# ver_2.net
KiCad netlist of a schematic drawn in EAGLE
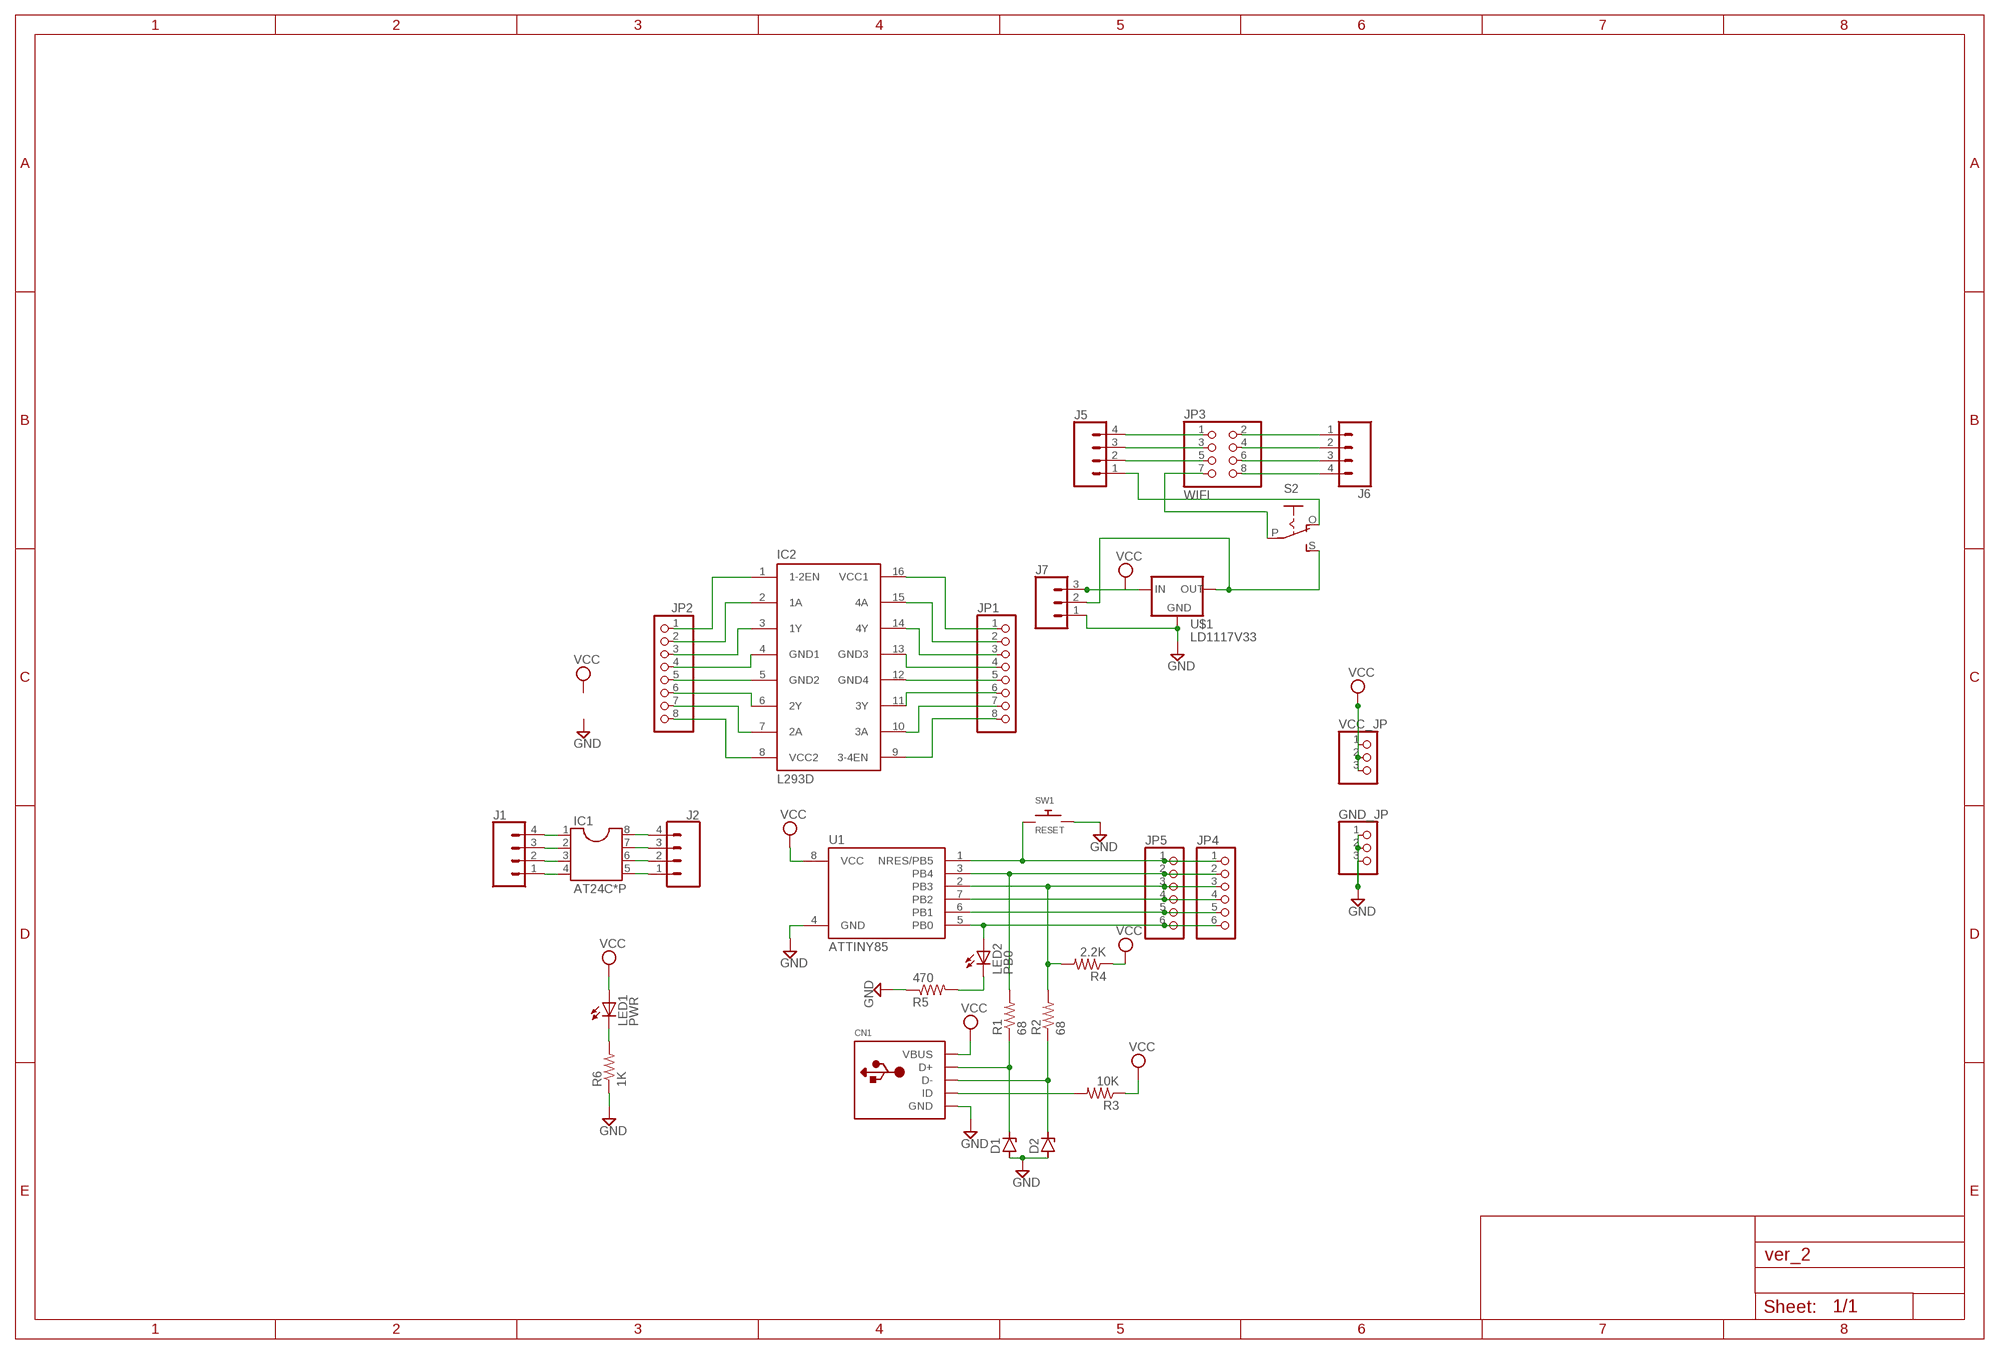
[diagram p0: schematic, sheet 1]

(export (version "E")
  (design (tool "Eeschema 10.0.6"))
  (components
    (comp (ref "CN1")
      (value "USBTHM")
      (footprint "eagle-import:USB-MINIB-THM")
      (libsource (lib "eagle-import") (part "USBTHM"))
    )
    (comp (ref "D1")
      (value "ZENER-DIODEDO34-7")
      (footprint "eagle-import:DO34Z7")
      (libsource (lib "eagle-import") (part "ZENER-DIODEDO34-7"))
    )
    (comp (ref "D2")
      (value "ZENER-DIODEDO34-7")
      (footprint "eagle-import:DO34Z7")
      (libsource (lib "eagle-import") (part "ZENER-DIODEDO34-7"))
    )
    (comp (ref "GND_JP")
      (value "PINHD-1X3")
      (footprint "eagle-import:1X03")
      (libsource (lib "eagle-import") (part "PINHD-1X3"))
    )
    (comp (ref "IC1")
      (value "AT24C*P")
      (footprint "eagle-import:SOCKET-08")
      (libsource (lib "eagle-import") (part "DIL8S"))
    )
    (comp (ref "IC2")
      (value "L293D")
      (footprint "eagle-import:DIL16")
      (libsource (lib "eagle-import") (part "L293D"))
    )
    (comp (ref "J1")
      (value "CONN_041X04_NO_SILK")
      (footprint "eagle-import:1X04_NO_SILK")
      (libsource (lib "eagle-import") (part "CONN_041X04_NO_SILK"))
    )
    (comp (ref "J2")
      (value "CONN_041X04_NO_SILK")
      (footprint "eagle-import:1X04_NO_SILK")
      (libsource (lib "eagle-import") (part "CONN_041X04_NO_SILK"))
    )
    (comp (ref "J5")
      (value "CONN_04PTH")
      (footprint "eagle-import:1X04")
      (libsource (lib "eagle-import") (part "CONN_04PTH"))
    )
    (comp (ref "J6")
      (value "CONN_04PTH")
      (footprint "eagle-import:1X04")
      (libsource (lib "eagle-import") (part "CONN_04PTH"))
    )
    (comp (ref "J7")
      (value "CONN_03")
      (footprint "eagle-import:1X03")
      (libsource (lib "eagle-import") (part "CONN_03"))
    )
    (comp (ref "JP1")
      (value "PINHD-1X8CLEANBIG")
      (footprint "eagle-import:1X08-CLEANBIG")
      (libsource (lib "eagle-import") (part "PINHD-1X8CLEANBIG"))
    )
    (comp (ref "JP2")
      (value "PINHD-1X8CLEANBIG")
      (footprint "eagle-import:1X08-CLEANBIG")
      (libsource (lib "eagle-import") (part "PINHD-1X8CLEANBIG"))
    )
    (comp (ref "JP3")
      (value "WIFI")
      (footprint "eagle-import:2X04")
      (libsource (lib "eagle-import") (part "PINHD-2X4"))
    )
    (comp (ref "JP4")
      (value "PINHD-1X6")
      (footprint "eagle-import:1X06")
      (libsource (lib "eagle-import") (part "PINHD-1X6"))
    )
    (comp (ref "JP5")
      (value "PINHD-1X6")
      (footprint "eagle-import:1X06")
      (libsource (lib "eagle-import") (part "PINHD-1X6"))
    )
    (comp (ref "LED1")
      (value "PWR")
      (footprint "eagle-import:LED3MM")
      (libsource (lib "eagle-import") (part "LED3MM"))
    )
    (comp (ref "LED2")
      (value "PB0")
      (footprint "eagle-import:LED3MM")
      (libsource (lib "eagle-import") (part "LED3MM"))
    )
    (comp (ref "R1")
      (value "68")
      (footprint "eagle-import:0204V")
      (libsource (lib "eagle-import") (part "R-US_0204/2V"))
    )
    (comp (ref "R2")
      (value "68")
      (footprint "eagle-import:0204V")
      (libsource (lib "eagle-import") (part "R-US_0204/2V"))
    )
    (comp (ref "R3")
      (value "10K")
      (footprint "eagle-import:0204V")
      (libsource (lib "eagle-import") (part "R-US_0204/2V"))
    )
    (comp (ref "R4")
      (value "2.2K")
      (footprint "eagle-import:0204V")
      (libsource (lib "eagle-import") (part "R-US_0204/2V"))
    )
    (comp (ref "R5")
      (value "470")
      (footprint "eagle-import:0204V")
      (libsource (lib "eagle-import") (part "R-US_0204/2V"))
    )
    (comp (ref "R6")
      (value "1K")
      (footprint "eagle-import:0204V")
      (libsource (lib "eagle-import") (part "R-US_0204/2V"))
    )
    (comp (ref "S2")
      (value "EG1218S")
      (footprint "eagle-import:EG1218")
      (libsource (lib "eagle-import") (part "EG1218S"))
    )
    (comp (ref "SW1")
      (value "RESET")
      (footprint "eagle-import:TACT_PANA-EVQ")
      (libsource (lib "eagle-import") (part "SWITCH_PUSHBUTTONEVQ-PE"))
    )
    (comp (ref "U$1")
      (value "LD1117V33")
      (footprint "eagle-import:LD1117V33")
      (libsource (lib "eagle-import") (part "LD1117V33"))
    )
    (comp (ref "U1")
      (value "ATTINY85")
      (footprint "eagle-import:PDIP08_300MIL")
      (libsource (lib "eagle-import") (part "ATTINY85P-20"))
    )
    (comp (ref "VCC_JP")
      (value "PINHD-1X3")
      (footprint "eagle-import:1X03")
      (libsource (lib "eagle-import") (part "PINHD-1X3"))
    )
  )
  (nets
    (net (code "1") (name "GND") (class "Default")
      (node (ref "CN1") (pin "GND") (pinfunction "GND_GND") (pintype "power_in"))
      (node (ref "D1") (pin "A") (pinfunction "A_A") (pintype "passive"))
      (node (ref "D2") (pin "A") (pinfunction "A_A") (pintype "passive"))
      (node (ref "GND_JP") (pin "1") (pinfunction "1_1") (pintype "passive"))
      (node (ref "GND_JP") (pin "2") (pinfunction "2_2") (pintype "passive"))
      (node (ref "GND_JP") (pin "3") (pinfunction "3_3") (pintype "passive"))
      (node (ref "J7") (pin "1") (pinfunction "1_1") (pintype "passive"))
      (node (ref "R5") (pin "1") (pinfunction "1_1") (pintype "passive"))
      (node (ref "R6") (pin "1") (pinfunction "1_1") (pintype "passive"))
      (node (ref "SW1") (pin "P$2") (pinfunction "P$2_P$2") (pintype "passive"))
      (node (ref "U$1") (pin "GND") (pinfunction "GND_GND") (pintype "input"))
      (node (ref "U1") (pin "4") (pinfunction "GND_4") (pintype "power_in"))
    )
    (net (code "2") (name "Net-(CN1-PadD+)") (class "Default")
      (node (ref "CN1") (pin "D+") (pinfunction "D+_D+") (pintype "bidirectional"))
      (node (ref "D1") (pin "C") (pinfunction "C_C") (pintype "passive"))
      (node (ref "R1") (pin "1") (pinfunction "1_1") (pintype "passive"))
    )
    (net (code "3") (name "Net-(CN1-PadD-)") (class "Default")
      (node (ref "CN1") (pin "D-") (pinfunction "D-_D-") (pintype "bidirectional"))
      (node (ref "D2") (pin "C") (pinfunction "C_C") (pintype "passive"))
      (node (ref "R2") (pin "1") (pinfunction "1_1") (pintype "passive"))
    )
    (net (code "4") (name "Net-(CN1-PadID)") (class "Default")
      (node (ref "CN1") (pin "ID") (pinfunction "ID_ID") (pintype "bidirectional"))
      (node (ref "R3") (pin "2") (pinfunction "2_2") (pintype "passive"))
    )
    (net (code "5") (name "Net-(IC1-Pad1)") (class "Default")
      (node (ref "IC1") (pin "1") (pinfunction "1_1") (pintype "passive"))
      (node (ref "J1") (pin "4") (pinfunction "4_4") (pintype "passive"))
    )
    (net (code "6") (name "Net-(IC1-Pad2)") (class "Default")
      (node (ref "IC1") (pin "2") (pinfunction "2_2") (pintype "passive"))
      (node (ref "J1") (pin "3") (pinfunction "3_3") (pintype "passive"))
    )
    (net (code "7") (name "Net-(IC1-Pad3)") (class "Default")
      (node (ref "IC1") (pin "3") (pinfunction "3_3") (pintype "passive"))
      (node (ref "J1") (pin "2") (pinfunction "2_2") (pintype "passive"))
    )
    (net (code "8") (name "Net-(IC1-Pad4)") (class "Default")
      (node (ref "IC1") (pin "4") (pinfunction "4_4") (pintype "passive"))
      (node (ref "J1") (pin "1") (pinfunction "1_1") (pintype "passive"))
    )
    (net (code "9") (name "Net-(IC1-Pad5)") (class "Default")
      (node (ref "IC1") (pin "5") (pinfunction "5_5") (pintype "passive"))
      (node (ref "J2") (pin "1") (pinfunction "1_1") (pintype "passive"))
    )
    (net (code "10") (name "Net-(IC1-Pad6)") (class "Default")
      (node (ref "IC1") (pin "6") (pinfunction "6_6") (pintype "passive"))
      (node (ref "J2") (pin "2") (pinfunction "2_2") (pintype "passive"))
    )
    (net (code "11") (name "Net-(IC1-Pad7)") (class "Default")
      (node (ref "IC1") (pin "7") (pinfunction "7_7") (pintype "passive"))
      (node (ref "J2") (pin "3") (pinfunction "3_3") (pintype "passive"))
    )
    (net (code "12") (name "Net-(IC1-Pad8)") (class "Default")
      (node (ref "IC1") (pin "8") (pinfunction "8_8") (pintype "passive"))
      (node (ref "J2") (pin "4") (pinfunction "4_4") (pintype "passive"))
    )
    (net (code "13") (name "Net-(IC2-1-2EN)") (class "Default")
      (node (ref "IC2") (pin "1") (pinfunction "1-2EN_1") (pintype "input"))
      (node (ref "JP2") (pin "1") (pinfunction "1_1") (pintype "passive"))
    )
    (net (code "14") (name "Net-(IC2-1A)") (class "Default")
      (node (ref "IC2") (pin "2") (pinfunction "1A_2") (pintype "input"))
      (node (ref "JP2") (pin "2") (pinfunction "2_2") (pintype "passive"))
    )
    (net (code "15") (name "Net-(IC2-1Y)") (class "Default")
      (node (ref "IC2") (pin "3") (pinfunction "1Y_3") (pintype "output"))
      (node (ref "JP2") (pin "3") (pinfunction "3_3") (pintype "passive"))
    )
    (net (code "16") (name "Net-(IC2-2A)") (class "Default")
      (node (ref "IC2") (pin "7") (pinfunction "2A_7") (pintype "input"))
      (node (ref "JP2") (pin "7") (pinfunction "7_7") (pintype "passive"))
    )
    (net (code "17") (name "Net-(IC2-2Y)") (class "Default")
      (node (ref "IC2") (pin "6") (pinfunction "2Y_6") (pintype "output"))
      (node (ref "JP2") (pin "6") (pinfunction "6_6") (pintype "passive"))
    )
    (net (code "18") (name "Net-(IC2-3-4EN)") (class "Default")
      (node (ref "IC2") (pin "9") (pinfunction "3-4EN_9") (pintype "input"))
      (node (ref "JP1") (pin "8") (pinfunction "8_8") (pintype "passive"))
    )
    (net (code "19") (name "Net-(IC2-3A)") (class "Default")
      (node (ref "IC2") (pin "10") (pinfunction "3A_10") (pintype "input"))
      (node (ref "JP1") (pin "7") (pinfunction "7_7") (pintype "passive"))
    )
    (net (code "20") (name "Net-(IC2-3Y)") (class "Default")
      (node (ref "IC2") (pin "11") (pinfunction "3Y_11") (pintype "output"))
      (node (ref "JP1") (pin "6") (pinfunction "6_6") (pintype "passive"))
    )
    (net (code "21") (name "Net-(IC2-4A)") (class "Default")
      (node (ref "IC2") (pin "15") (pinfunction "4A_15") (pintype "input"))
      (node (ref "JP1") (pin "2") (pinfunction "2_2") (pintype "passive"))
    )
    (net (code "22") (name "Net-(IC2-4Y)") (class "Default")
      (node (ref "IC2") (pin "14") (pinfunction "4Y_14") (pintype "output"))
      (node (ref "JP1") (pin "3") (pinfunction "3_3") (pintype "passive"))
    )
    (net (code "23") (name "Net-(IC2-GND1)") (class "Default")
      (node (ref "IC2") (pin "4") (pinfunction "GND1_4") (pintype "power_in"))
      (node (ref "JP2") (pin "4") (pinfunction "4_4") (pintype "passive"))
    )
    (net (code "24") (name "Net-(IC2-GND2)") (class "Default")
      (node (ref "IC2") (pin "5") (pinfunction "GND2_5") (pintype "power_in"))
      (node (ref "JP2") (pin "5") (pinfunction "5_5") (pintype "passive"))
    )
    (net (code "25") (name "Net-(IC2-GND3)") (class "Default")
      (node (ref "IC2") (pin "13") (pinfunction "GND3_13") (pintype "power_in"))
      (node (ref "JP1") (pin "4") (pinfunction "4_4") (pintype "passive"))
    )
    (net (code "26") (name "Net-(IC2-GND4)") (class "Default")
      (node (ref "IC2") (pin "12") (pinfunction "GND4_12") (pintype "power_in"))
      (node (ref "JP1") (pin "5") (pinfunction "5_5") (pintype "passive"))
    )
    (net (code "27") (name "Net-(IC2-VCC1)") (class "Default")
      (node (ref "IC2") (pin "16") (pinfunction "VCC1_16") (pintype "power_in"))
      (node (ref "JP1") (pin "1") (pinfunction "1_1") (pintype "passive"))
    )
    (net (code "28") (name "Net-(IC2-VCC2)") (class "Default")
      (node (ref "IC2") (pin "8") (pinfunction "VCC2_8") (pintype "power_in"))
      (node (ref "JP2") (pin "8") (pinfunction "8_8") (pintype "passive"))
    )
    (net (code "29") (name "Net-(J5-Pad1)") (class "Default")
      (node (ref "J5") (pin "1") (pinfunction "1_1") (pintype "passive"))
      (node (ref "S2") (pin "O") (pinfunction "O_O") (pintype "passive"))
    )
    (net (code "30") (name "Net-(J5-Pad2)") (class "Default")
      (node (ref "J5") (pin "2") (pinfunction "2_2") (pintype "passive"))
      (node (ref "JP3") (pin "5") (pinfunction "5_5") (pintype "passive"))
    )
    (net (code "31") (name "Net-(J5-Pad3)") (class "Default")
      (node (ref "J5") (pin "3") (pinfunction "3_3") (pintype "passive"))
      (node (ref "JP3") (pin "3") (pinfunction "3_3") (pintype "passive"))
    )
    (net (code "32") (name "Net-(J5-Pad4)") (class "Default")
      (node (ref "J5") (pin "4") (pinfunction "4_4") (pintype "passive"))
      (node (ref "JP3") (pin "1") (pinfunction "1_1") (pintype "passive"))
    )
    (net (code "33") (name "Net-(J6-Pad1)") (class "Default")
      (node (ref "J6") (pin "1") (pinfunction "1_1") (pintype "passive"))
      (node (ref "JP3") (pin "2") (pinfunction "2_2") (pintype "passive"))
    )
    (net (code "34") (name "Net-(J6-Pad2)") (class "Default")
      (node (ref "J6") (pin "2") (pinfunction "2_2") (pintype "passive"))
      (node (ref "JP3") (pin "4") (pinfunction "4_4") (pintype "passive"))
    )
    (net (code "35") (name "Net-(J6-Pad3)") (class "Default")
      (node (ref "J6") (pin "3") (pinfunction "3_3") (pintype "passive"))
      (node (ref "JP3") (pin "6") (pinfunction "6_6") (pintype "passive"))
    )
    (net (code "36") (name "Net-(J6-Pad4)") (class "Default")
      (node (ref "J6") (pin "4") (pinfunction "4_4") (pintype "passive"))
      (node (ref "JP3") (pin "8") (pinfunction "8_8") (pintype "passive"))
    )
    (net (code "37") (name "Net-(J7-Pad2)") (class "Default")
      (node (ref "J7") (pin "2") (pinfunction "2_2") (pintype "passive"))
      (node (ref "S2") (pin "S") (pinfunction "S_S") (pintype "passive"))
      (node (ref "U$1") (pin "OUT") (pinfunction "OUT_OUT") (pintype "output"))
    )
    (net (code "38") (name "Net-(JP3-Pad7)") (class "Default")
      (node (ref "JP3") (pin "7") (pinfunction "7_7") (pintype "passive"))
      (node (ref "S2") (pin "P") (pinfunction "P_P") (pintype "passive"))
    )
    (net (code "39") (name "Net-(LED1-C)") (class "Default")
      (node (ref "LED1") (pin "K") (pinfunction "C_K") (pintype "passive"))
      (node (ref "R6") (pin "2") (pinfunction "2_2") (pintype "passive"))
    )
    (net (code "40") (name "Net-(LED2-C)") (class "Default")
      (node (ref "LED2") (pin "K") (pinfunction "C_K") (pintype "passive"))
      (node (ref "R5") (pin "2") (pinfunction "2_2") (pintype "passive"))
    )
    (net (code "41") (name "Net-(U1-NRES{slash}PB5)") (class "Default")
      (node (ref "JP4") (pin "1") (pinfunction "1_1") (pintype "passive"))
      (node (ref "JP5") (pin "1") (pinfunction "1_1") (pintype "passive"))
      (node (ref "SW1") (pin "P$1") (pinfunction "P$1_P$1") (pintype "passive"))
      (node (ref "U1") (pin "1") (pinfunction "NRES/PB5_1") (pintype "bidirectional"))
    )
    (net (code "42") (name "Net-(U1-PB0)") (class "Default")
      (node (ref "JP4") (pin "6") (pinfunction "6_6") (pintype "passive"))
      (node (ref "JP5") (pin "6") (pinfunction "6_6") (pintype "passive"))
      (node (ref "LED2") (pin "A") (pinfunction "A_A") (pintype "passive"))
      (node (ref "U1") (pin "5") (pinfunction "PB0_5") (pintype "bidirectional"))
    )
    (net (code "43") (name "Net-(U1-PB1)") (class "Default")
      (node (ref "JP4") (pin "5") (pinfunction "5_5") (pintype "passive"))
      (node (ref "JP5") (pin "5") (pinfunction "5_5") (pintype "passive"))
      (node (ref "U1") (pin "6") (pinfunction "PB1_6") (pintype "bidirectional"))
    )
    (net (code "44") (name "Net-(U1-PB2)") (class "Default")
      (node (ref "JP4") (pin "4") (pinfunction "4_4") (pintype "passive"))
      (node (ref "JP5") (pin "4") (pinfunction "4_4") (pintype "passive"))
      (node (ref "U1") (pin "7") (pinfunction "PB2_7") (pintype "bidirectional"))
    )
    (net (code "45") (name "Net-(U1-PB3)") (class "Default")
      (node (ref "JP4") (pin "3") (pinfunction "3_3") (pintype "passive"))
      (node (ref "JP5") (pin "3") (pinfunction "3_3") (pintype "passive"))
      (node (ref "R2") (pin "2") (pinfunction "2_2") (pintype "passive"))
      (node (ref "R4") (pin "2") (pinfunction "2_2") (pintype "passive"))
      (node (ref "U1") (pin "2") (pinfunction "PB3_2") (pintype "bidirectional"))
    )
    (net (code "46") (name "Net-(U1-PB4)") (class "Default")
      (node (ref "JP4") (pin "2") (pinfunction "2_2") (pintype "passive"))
      (node (ref "JP5") (pin "2") (pinfunction "2_2") (pintype "passive"))
      (node (ref "R1") (pin "2") (pinfunction "2_2") (pintype "passive"))
      (node (ref "U1") (pin "3") (pinfunction "PB4_3") (pintype "bidirectional"))
    )
    (net (code "47") (name "VCC") (class "Default")
      (node (ref "CN1") (pin "VBUS") (pinfunction "VBUS_VBUS") (pintype "power_in"))
      (node (ref "J7") (pin "3") (pinfunction "3_3") (pintype "passive"))
      (node (ref "LED1") (pin "A") (pinfunction "A_A") (pintype "passive"))
      (node (ref "R3") (pin "1") (pinfunction "1_1") (pintype "passive"))
      (node (ref "R4") (pin "1") (pinfunction "1_1") (pintype "passive"))
      (node (ref "U$1") (pin "IN") (pinfunction "IN_IN") (pintype "input"))
      (node (ref "U1") (pin "8") (pinfunction "VCC_8") (pintype "power_in"))
      (node (ref "VCC_JP") (pin "1") (pinfunction "1_1") (pintype "passive"))
      (node (ref "VCC_JP") (pin "2") (pinfunction "2_2") (pintype "passive"))
      (node (ref "VCC_JP") (pin "3") (pinfunction "3_3") (pintype "passive"))
    )
  )
)
